# module-tpa3125.net
KiCad netlist of a schematic drawn in EAGLE
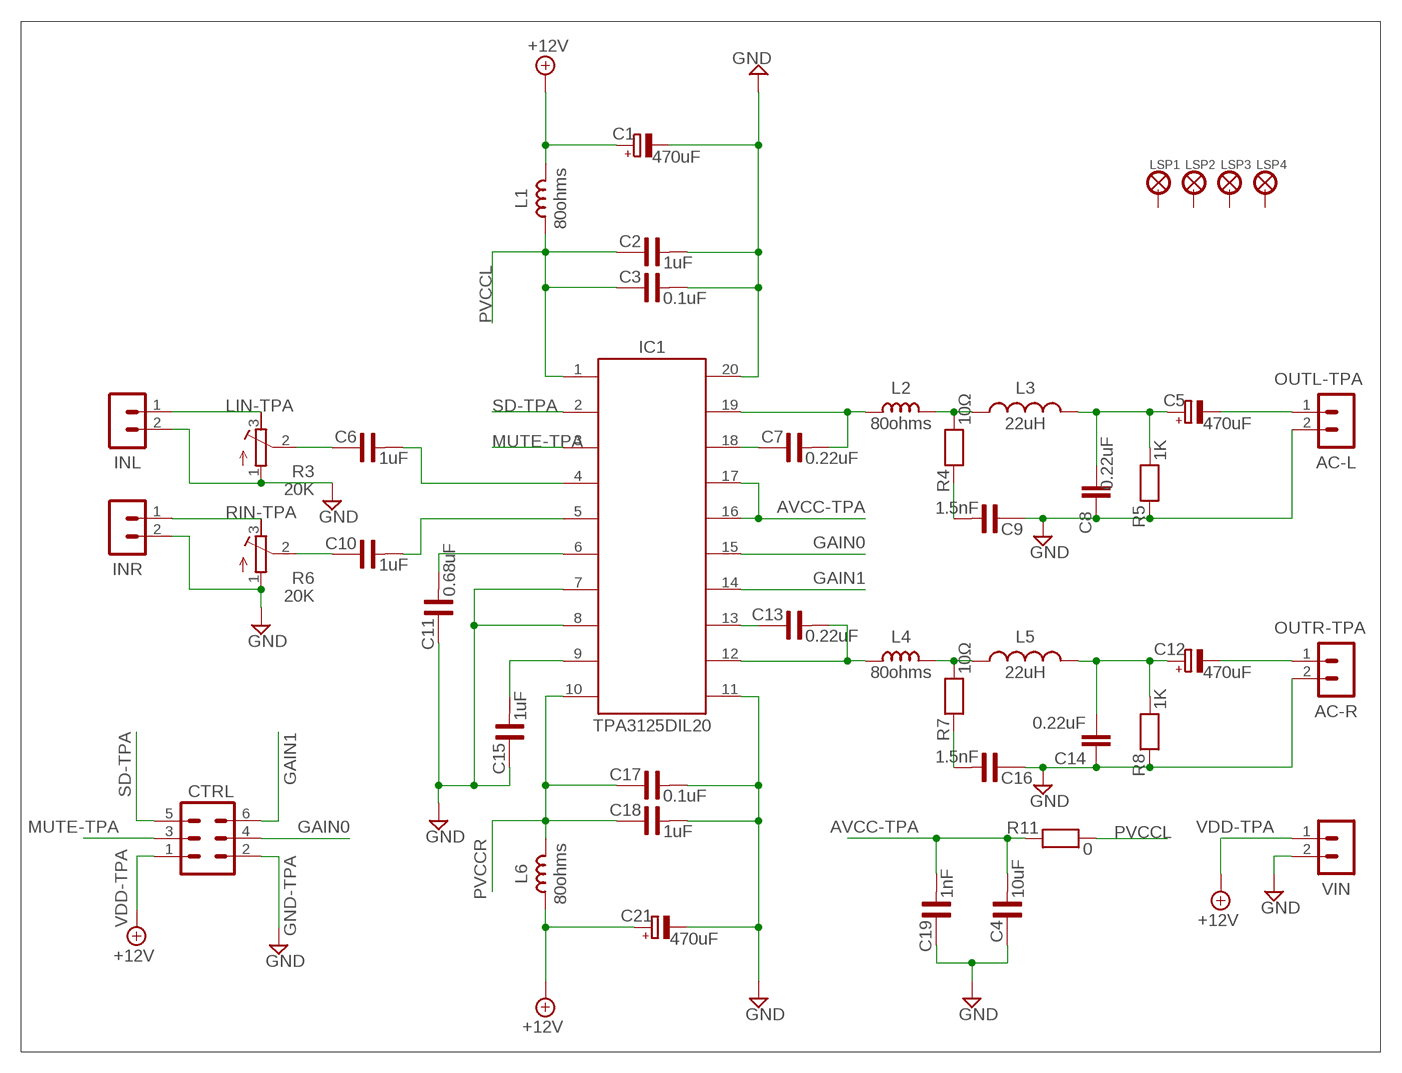
[diagram p0: schematic, sheet 1]

(export (version "E")
  (design (tool "Eeschema 10.0.6"))
  (components
    (comp (ref "AC-L")
      (value "MA02-1GREEN")
      (footprint "eagle-import:MA02-1-GREEN")
      (libsource (lib "eagle-import") (part "MA02-1GREEN"))
    )
    (comp (ref "AC-R")
      (value "MA02-1GREEN")
      (footprint "eagle-import:MA02-1-GREEN")
      (libsource (lib "eagle-import") (part "MA02-1GREEN"))
    )
    (comp (ref "C1")
      (value "470uF")
      (footprint "eagle-import:E5-10,5")
      (libsource (lib "eagle-import") (part "CPOL-EUE5-10.5"))
    )
    (comp (ref "C2")
      (value "1uF")
      (footprint "eagle-import:C1206")
      (libsource (lib "eagle-import") (part "C-US1206"))
    )
    (comp (ref "C3")
      (value "0.1uF")
      (footprint "eagle-import:C0805")
      (libsource (lib "eagle-import") (part "C-US0805"))
    )
    (comp (ref "C4")
      (value "10uF")
      (footprint "eagle-import:C0805")
      (libsource (lib "eagle-import") (part "C-US0805"))
    )
    (comp (ref "C5")
      (value "470uF")
      (footprint "eagle-import:E5-10,5")
      (libsource (lib "eagle-import") (part "CPOL-EUE5-10.5"))
    )
    (comp (ref "C6")
      (value "1uF")
      (footprint "eagle-import:C1206")
      (libsource (lib "eagle-import") (part "C-US1206"))
    )
    (comp (ref "C7")
      (value "0.22uF")
      (footprint "eagle-import:C0805")
      (libsource (lib "eagle-import") (part "C-US0805"))
    )
    (comp (ref "C8")
      (value "0.22uF")
      (footprint "eagle-import:C050-050X075")
      (libsource (lib "eagle-import") (part "C-EU050-050X075"))
    )
    (comp (ref "C9")
      (value "1.5nF")
      (footprint "eagle-import:C0805")
      (libsource (lib "eagle-import") (part "C-US0805"))
    )
    (comp (ref "C10")
      (value "1uF")
      (footprint "eagle-import:C1206")
      (libsource (lib "eagle-import") (part "C-US1206"))
    )
    (comp (ref "C11")
      (value "0.68uF")
      (footprint "eagle-import:C0805")
      (libsource (lib "eagle-import") (part "C-US0805"))
    )
    (comp (ref "C12")
      (value "470uF")
      (footprint "eagle-import:E5-10,5")
      (libsource (lib "eagle-import") (part "CPOL-EUE5-10.5"))
    )
    (comp (ref "C13")
      (value "0.22uF")
      (footprint "eagle-import:C0805")
      (libsource (lib "eagle-import") (part "C-US0805"))
    )
    (comp (ref "C14")
      (value "0.22uF")
      (footprint "eagle-import:C050-050X075")
      (libsource (lib "eagle-import") (part "C-EU050-050X075"))
    )
    (comp (ref "C15")
      (value "1uF")
      (footprint "eagle-import:C0805")
      (libsource (lib "eagle-import") (part "C-US0805"))
    )
    (comp (ref "C16")
      (value "1.5nF")
      (footprint "eagle-import:C0805")
      (libsource (lib "eagle-import") (part "C-US0805"))
    )
    (comp (ref "C17")
      (value "0.1uF")
      (footprint "eagle-import:C0805")
      (libsource (lib "eagle-import") (part "C-US0805"))
    )
    (comp (ref "C18")
      (value "1uF")
      (footprint "eagle-import:C1206")
      (libsource (lib "eagle-import") (part "C-US1206"))
    )
    (comp (ref "C19")
      (value "1nF")
      (footprint "eagle-import:C0805")
      (libsource (lib "eagle-import") (part "C-US0805"))
    )
    (comp (ref "C21")
      (value "470uF")
      (footprint "eagle-import:E5-10,5")
      (libsource (lib "eagle-import") (part "CPOL-EUE5-10.5"))
    )
    (comp (ref "CTRL")
      (value "MA03-2")
      (footprint "eagle-import:MA03-2")
      (libsource (lib "eagle-import") (part "MA03-2"))
    )
    (comp (ref "IC1")
      (value "TPA3125DIL20")
      (footprint "eagle-import:DIL20")
      (libsource (lib "eagle-import") (part "TPA3125DIL20"))
    )
    (comp (ref "INL")
      (value "MA02-1GREEN")
      (footprint "eagle-import:MA02-1-GREEN")
      (libsource (lib "eagle-import") (part "MA02-1GREEN"))
    )
    (comp (ref "INR")
      (value "MA02-1GREEN")
      (footprint "eagle-import:MA02-1-GREEN")
      (libsource (lib "eagle-import") (part "MA02-1GREEN"))
    )
    (comp (ref "L1")
      (value "80ohms")
      (footprint "eagle-import:L0805")
      (libsource (lib "eagle-import") (part "L-USL0805"))
    )
    (comp (ref "L2")
      (value "80ohms")
      (footprint "eagle-import:L0805")
      (libsource (lib "eagle-import") (part "L-USL0805"))
    )
    (comp (ref "L3")
      (value "22uH")
      (footprint "eagle-import:6000-XXXX-RC")
      (libsource (lib "eagle-import") (part "L-US6000-XXX-RC"))
    )
    (comp (ref "L4")
      (value "80ohms")
      (footprint "eagle-import:L0805")
      (libsource (lib "eagle-import") (part "L-USL0805"))
    )
    (comp (ref "L5")
      (value "22uH")
      (footprint "eagle-import:6000-XXXX-RC")
      (libsource (lib "eagle-import") (part "L-US6000-XXX-RC"))
    )
    (comp (ref "L6")
      (value "80ohms")
      (footprint "eagle-import:L0805")
      (libsource (lib "eagle-import") (part "L-USL0805"))
    )
    (comp (ref "LSP1")
      (value "LSP27")
      (footprint "eagle-import:LSP27")
      (libsource (lib "eagle-import") (part "LSP27"))
    )
    (comp (ref "LSP2")
      (value "LSP27")
      (footprint "eagle-import:LSP27")
      (libsource (lib "eagle-import") (part "LSP27"))
    )
    (comp (ref "LSP3")
      (value "LSP27")
      (footprint "eagle-import:LSP27")
      (libsource (lib "eagle-import") (part "LSP27"))
    )
    (comp (ref "LSP4")
      (value "LSP27")
      (footprint "eagle-import:LSP27")
      (libsource (lib "eagle-import") (part "LSP27"))
    )
    (comp (ref "R3")
      (value "20K")
      (footprint "eagle-import:PV32H")
      (libsource (lib "eagle-import") (part "PV32H"))
    )
    (comp (ref "R4")
      (value "10Ω")
      (footprint "eagle-import:R0805")
      (libsource (lib "eagle-import") (part "R-US0805"))
    )
    (comp (ref "R5")
      (value "1K")
      (footprint "eagle-import:R0805")
      (libsource (lib "eagle-import") (part "R-US0805"))
    )
    (comp (ref "R6")
      (value "20K")
      (footprint "eagle-import:PV32H")
      (libsource (lib "eagle-import") (part "PV32H"))
    )
    (comp (ref "R7")
      (value "10Ω")
      (footprint "eagle-import:R0805")
      (libsource (lib "eagle-import") (part "R-US0805"))
    )
    (comp (ref "R8")
      (value "1K")
      (footprint "eagle-import:R0805")
      (libsource (lib "eagle-import") (part "R-US0805"))
    )
    (comp (ref "R11")
      (value "0")
      (footprint "eagle-import:R0805")
      (libsource (lib "eagle-import") (part "R-US0805"))
    )
    (comp (ref "VIN")
      (value "MA02-1GREEN")
      (footprint "eagle-import:MA02-1-GREEN")
      (libsource (lib "eagle-import") (part "MA02-1GREEN"))
    )
  )
  (nets
    (net (code "1") (name "+12V") (class "Default")
      (node (ref "C1") (pin "+") (pinfunction "+_+") (pintype "passive"))
      (node (ref "C21") (pin "+") (pinfunction "+_+") (pintype "passive"))
      (node (ref "CTRL") (pin "1") (pinfunction "1_1") (pintype "passive"))
      (node (ref "L1") (pin "2") (pinfunction "2_2") (pintype "passive"))
      (node (ref "L6") (pin "1") (pinfunction "1_1") (pintype "passive"))
      (node (ref "VIN") (pin "1") (pinfunction "1_1") (pintype "passive"))
    )
    (net (code "2") (name "/AVCC-TPA") (class "Default")
      (node (ref "C19") (pin "2") (pinfunction "2_2") (pintype "passive"))
      (node (ref "C4") (pin "2") (pinfunction "2_2") (pintype "passive"))
      (node (ref "IC1") (pin "16") (pinfunction "P$16_16") (pintype "bidirectional"))
      (node (ref "IC1") (pin "17") (pinfunction "P$17_17") (pintype "bidirectional"))
      (node (ref "R11") (pin "1") (pinfunction "1_1") (pintype "passive"))
    )
    (net (code "3") (name "/GAIN0") (class "Default")
      (node (ref "CTRL") (pin "4") (pinfunction "4_4") (pintype "passive"))
      (node (ref "IC1") (pin "15") (pinfunction "P$15_15") (pintype "bidirectional"))
    )
    (net (code "4") (name "/GAIN1") (class "Default")
      (node (ref "CTRL") (pin "6") (pinfunction "6_6") (pintype "passive"))
      (node (ref "IC1") (pin "14") (pinfunction "P$14_14") (pintype "bidirectional"))
    )
    (net (code "5") (name "/LIN-TPA") (class "Default")
      (node (ref "INL") (pin "1") (pinfunction "1_1") (pintype "passive"))
      (node (ref "R3") (pin "3") (pinfunction "3_3") (pintype "passive"))
    )
    (net (code "6") (name "/MUTE-TPA") (class "Default")
      (node (ref "CTRL") (pin "3") (pinfunction "3_3") (pintype "passive"))
      (node (ref "IC1") (pin "3") (pinfunction "P$3_3") (pintype "bidirectional"))
    )
    (net (code "7") (name "/OUTL-TPA") (class "Default")
      (node (ref "AC-L") (pin "1") (pinfunction "1_1") (pintype "passive"))
      (node (ref "C5") (pin "-") (pinfunction "-_-") (pintype "passive"))
    )
    (net (code "8") (name "/OUTR-TPA") (class "Default")
      (node (ref "AC-R") (pin "1") (pinfunction "1_1") (pintype "passive"))
      (node (ref "C12") (pin "-") (pinfunction "-_-") (pintype "passive"))
    )
    (net (code "9") (name "/PVCCL") (class "Default")
      (node (ref "C2") (pin "1") (pinfunction "1_1") (pintype "passive"))
      (node (ref "C3") (pin "1") (pinfunction "1_1") (pintype "passive"))
      (node (ref "IC1") (pin "1") (pinfunction "P$1_1") (pintype "bidirectional"))
      (node (ref "L1") (pin "1") (pinfunction "1_1") (pintype "passive"))
      (node (ref "R11") (pin "2") (pinfunction "2_2") (pintype "passive"))
    )
    (net (code "10") (name "/PVCCR") (class "Default")
      (node (ref "C17") (pin "1") (pinfunction "1_1") (pintype "passive"))
      (node (ref "C18") (pin "1") (pinfunction "1_1") (pintype "passive"))
      (node (ref "IC1") (pin "10") (pinfunction "P$10_10") (pintype "bidirectional"))
      (node (ref "L6") (pin "2") (pinfunction "2_2") (pintype "passive"))
    )
    (net (code "11") (name "/RIN-TPA") (class "Default")
      (node (ref "INR") (pin "1") (pinfunction "1_1") (pintype "passive"))
      (node (ref "R6") (pin "3") (pinfunction "3_3") (pintype "passive"))
    )
    (net (code "12") (name "/SD-TPA") (class "Default")
      (node (ref "CTRL") (pin "5") (pinfunction "5_5") (pintype "passive"))
      (node (ref "IC1") (pin "2") (pinfunction "P$2_2") (pintype "bidirectional"))
    )
    (net (code "13") (name "GND") (class "Default")
      (node (ref "AC-L") (pin "2") (pinfunction "2_2") (pintype "passive"))
      (node (ref "AC-R") (pin "2") (pinfunction "2_2") (pintype "passive"))
      (node (ref "C1") (pin "-") (pinfunction "-_-") (pintype "passive"))
      (node (ref "C11") (pin "1") (pinfunction "1_1") (pintype "passive"))
      (node (ref "C14") (pin "1") (pinfunction "1_1") (pintype "passive"))
      (node (ref "C15") (pin "1") (pinfunction "1_1") (pintype "passive"))
      (node (ref "C16") (pin "1") (pinfunction "1_1") (pintype "passive"))
      (node (ref "C17") (pin "2") (pinfunction "2_2") (pintype "passive"))
      (node (ref "C18") (pin "2") (pinfunction "2_2") (pintype "passive"))
      (node (ref "C19") (pin "1") (pinfunction "1_1") (pintype "passive"))
      (node (ref "C2") (pin "2") (pinfunction "2_2") (pintype "passive"))
      (node (ref "C21") (pin "-") (pinfunction "-_-") (pintype "passive"))
      (node (ref "C3") (pin "2") (pinfunction "2_2") (pintype "passive"))
      (node (ref "C4") (pin "1") (pinfunction "1_1") (pintype "passive"))
      (node (ref "C8") (pin "1") (pinfunction "1_1") (pintype "passive"))
      (node (ref "C9") (pin "1") (pinfunction "1_1") (pintype "passive"))
      (node (ref "CTRL") (pin "2") (pinfunction "2_2") (pintype "passive"))
      (node (ref "IC1") (pin "11") (pinfunction "P$11_11") (pintype "bidirectional"))
      (node (ref "IC1") (pin "20") (pinfunction "P$20_20") (pintype "bidirectional"))
      (node (ref "IC1") (pin "7") (pinfunction "P$7_7") (pintype "bidirectional"))
      (node (ref "IC1") (pin "8") (pinfunction "P$8_8") (pintype "bidirectional"))
      (node (ref "INL") (pin "2") (pinfunction "2_2") (pintype "passive"))
      (node (ref "INR") (pin "2") (pinfunction "2_2") (pintype "passive"))
      (node (ref "R3") (pin "1") (pinfunction "1_1") (pintype "passive"))
      (node (ref "R5") (pin "1") (pinfunction "1_1") (pintype "passive"))
      (node (ref "R6") (pin "1") (pinfunction "1_1") (pintype "passive"))
      (node (ref "R8") (pin "1") (pinfunction "1_1") (pintype "passive"))
      (node (ref "VIN") (pin "2") (pinfunction "2_2") (pintype "passive"))
    )
    (net (code "14") (name "Net-(C5-Pad+)") (class "Default")
      (node (ref "C5") (pin "+") (pinfunction "+_+") (pintype "passive"))
      (node (ref "C8") (pin "2") (pinfunction "2_2") (pintype "passive"))
      (node (ref "L3") (pin "2") (pinfunction "2_2") (pintype "passive"))
      (node (ref "R5") (pin "2") (pinfunction "2_2") (pintype "passive"))
    )
    (net (code "15") (name "Net-(C6-Pad1)") (class "Default")
      (node (ref "C6") (pin "1") (pinfunction "1_1") (pintype "passive"))
      (node (ref "R3") (pin "2") (pinfunction "2_2") (pintype "passive"))
    )
    (net (code "16") (name "Net-(C9-Pad2)") (class "Default")
      (node (ref "C9") (pin "2") (pinfunction "2_2") (pintype "passive"))
      (node (ref "R4") (pin "1") (pinfunction "1_1") (pintype "passive"))
    )
    (net (code "17") (name "Net-(C10-Pad1)") (class "Default")
      (node (ref "C10") (pin "1") (pinfunction "1_1") (pintype "passive"))
      (node (ref "R6") (pin "2") (pinfunction "2_2") (pintype "passive"))
    )
    (net (code "18") (name "Net-(C12-Pad+)") (class "Default")
      (node (ref "C12") (pin "+") (pinfunction "+_+") (pintype "passive"))
      (node (ref "C14") (pin "2") (pinfunction "2_2") (pintype "passive"))
      (node (ref "L5") (pin "2") (pinfunction "2_2") (pintype "passive"))
      (node (ref "R8") (pin "2") (pinfunction "2_2") (pintype "passive"))
    )
    (net (code "19") (name "Net-(C16-Pad2)") (class "Default")
      (node (ref "C16") (pin "2") (pinfunction "2_2") (pintype "passive"))
      (node (ref "R7") (pin "1") (pinfunction "1_1") (pintype "passive"))
    )
    (net (code "20") (name "Net-(IC1-P$4)") (class "Default")
      (node (ref "C6") (pin "2") (pinfunction "2_2") (pintype "passive"))
      (node (ref "IC1") (pin "4") (pinfunction "P$4_4") (pintype "bidirectional"))
    )
    (net (code "21") (name "Net-(IC1-P$5)") (class "Default")
      (node (ref "C10") (pin "2") (pinfunction "2_2") (pintype "passive"))
      (node (ref "IC1") (pin "5") (pinfunction "P$5_5") (pintype "bidirectional"))
    )
    (net (code "22") (name "Net-(IC1-P$6)") (class "Default")
      (node (ref "C11") (pin "2") (pinfunction "2_2") (pintype "passive"))
      (node (ref "IC1") (pin "6") (pinfunction "P$6_6") (pintype "bidirectional"))
    )
    (net (code "23") (name "Net-(IC1-P$9)") (class "Default")
      (node (ref "C15") (pin "2") (pinfunction "2_2") (pintype "passive"))
      (node (ref "IC1") (pin "9") (pinfunction "P$9_9") (pintype "bidirectional"))
    )
    (net (code "24") (name "Net-(IC1-P$12)") (class "Default")
      (node (ref "C13") (pin "2") (pinfunction "2_2") (pintype "passive"))
      (node (ref "IC1") (pin "12") (pinfunction "P$12_12") (pintype "bidirectional"))
      (node (ref "L4") (pin "1") (pinfunction "1_1") (pintype "passive"))
    )
    (net (code "25") (name "Net-(IC1-P$13)") (class "Default")
      (node (ref "C13") (pin "1") (pinfunction "1_1") (pintype "passive"))
      (node (ref "IC1") (pin "13") (pinfunction "P$13_13") (pintype "bidirectional"))
    )
    (net (code "26") (name "Net-(IC1-P$18)") (class "Default")
      (node (ref "C7") (pin "1") (pinfunction "1_1") (pintype "passive"))
      (node (ref "IC1") (pin "18") (pinfunction "P$18_18") (pintype "bidirectional"))
    )
    (net (code "27") (name "Net-(IC1-P$19)") (class "Default")
      (node (ref "C7") (pin "2") (pinfunction "2_2") (pintype "passive"))
      (node (ref "IC1") (pin "19") (pinfunction "P$19_19") (pintype "bidirectional"))
      (node (ref "L2") (pin "1") (pinfunction "1_1") (pintype "passive"))
    )
    (net (code "28") (name "Net-(L2-Pad2)") (class "Default")
      (node (ref "L2") (pin "2") (pinfunction "2_2") (pintype "passive"))
      (node (ref "L3") (pin "1") (pinfunction "1_1") (pintype "passive"))
      (node (ref "R4") (pin "2") (pinfunction "2_2") (pintype "passive"))
    )
    (net (code "29") (name "Net-(L4-Pad2)") (class "Default")
      (node (ref "L4") (pin "2") (pinfunction "2_2") (pintype "passive"))
      (node (ref "L5") (pin "1") (pinfunction "1_1") (pintype "passive"))
      (node (ref "R7") (pin "2") (pinfunction "2_2") (pintype "passive"))
    )
    (net (code "30") (name "unconnected-(LSP1-PadMP)") (class "Default")
      (node (ref "LSP1") (pin "MP") (pinfunction "MP_MP") (pintype "passive"))
    )
    (net (code "31") (name "unconnected-(LSP2-PadMP)") (class "Default")
      (node (ref "LSP2") (pin "MP") (pinfunction "MP_MP") (pintype "passive"))
    )
    (net (code "32") (name "unconnected-(LSP3-PadMP)") (class "Default")
      (node (ref "LSP3") (pin "MP") (pinfunction "MP_MP") (pintype "passive"))
    )
    (net (code "33") (name "unconnected-(LSP4-PadMP)") (class "Default")
      (node (ref "LSP4") (pin "MP") (pinfunction "MP_MP") (pintype "passive"))
    )
  )
)
